# IOa.net
KiCad netlist of a schematic drawn in Altium Designer
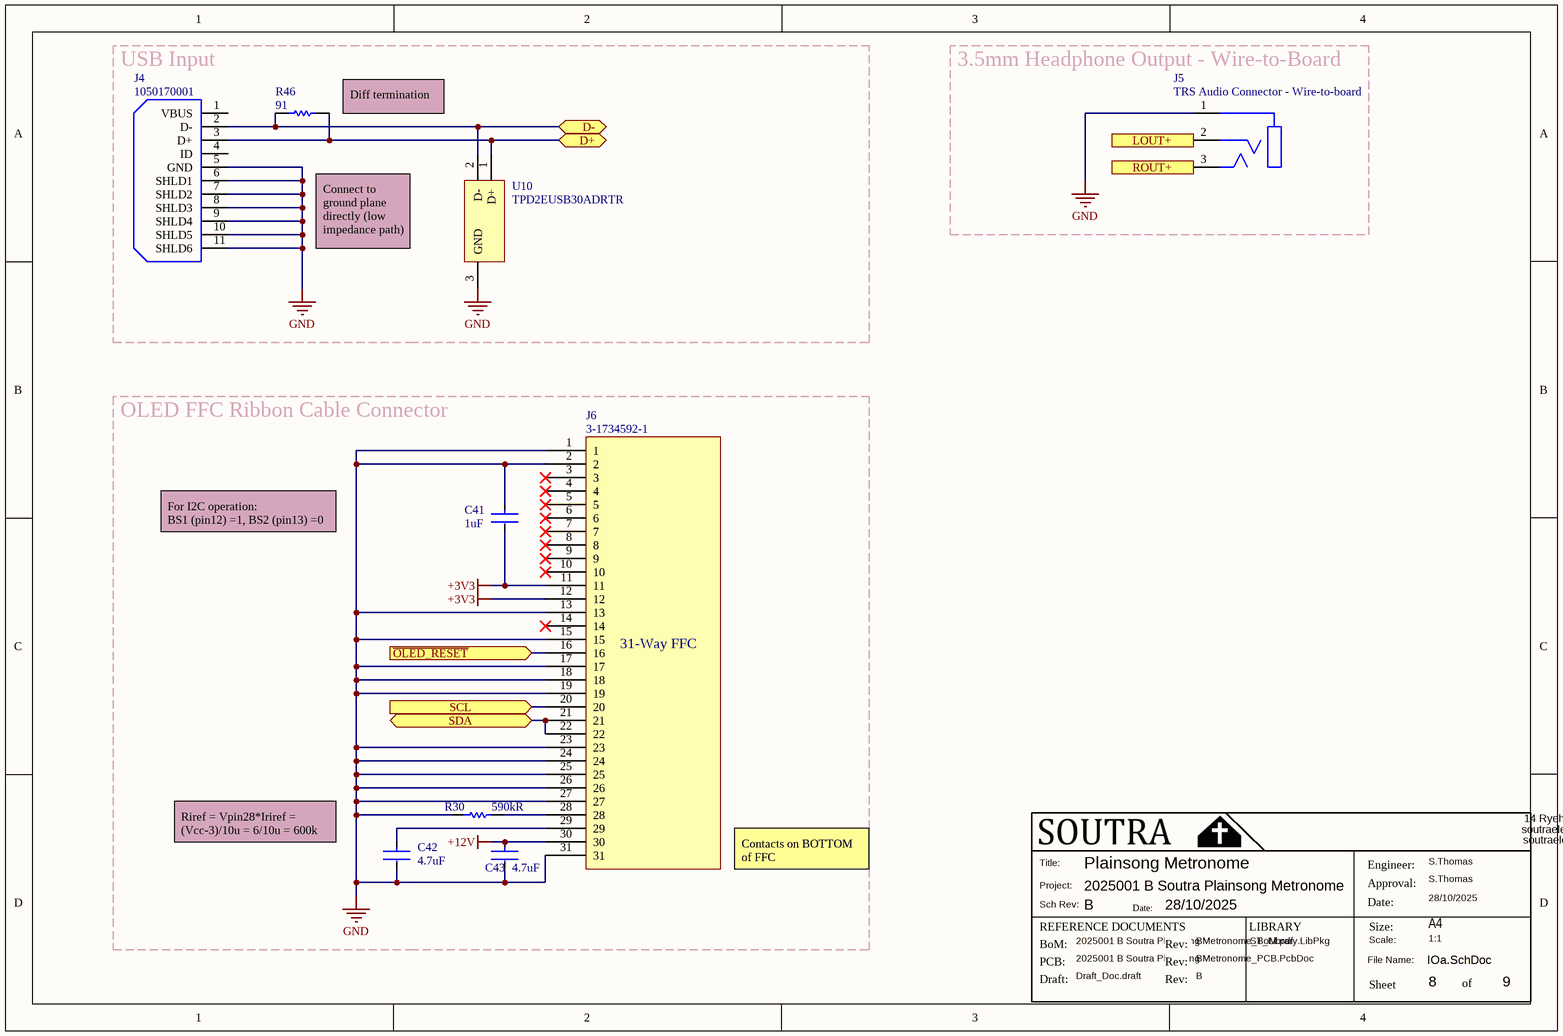
[diagram p0: IOa.SchDoc]

(export (version "E")
  (design (tool "Eeschema 10.0.6"))
  (components
    (comp (ref "C41")
      (value "1uF")
      (footprint "CAPC1005X06L")
      (fields
        (field (name "MANUFACTURER") "Yageo")
        (field (name "MANUFACTURER PART NUMBER") "CC0402KRX5R6BB105")
        (field (name "ALTERNATIVE PART") "0402ZD105KAT2A")
      )
      (libsource (lib "ST_Library") (part "CC0402KRX5R6BB105"))
    )
    (comp (ref "C42")
      (value "4.7uF")
      (footprint "CC1206-IPC_A")
      (fields
        (field (name "MANUFACTURER") "Samsung")
        (field (name "MANUFACTURER PART NUMBER") "CL31B475KAHNNNE")
      )
      (libsource (lib "ST_Library") (part "CL31B475KAHNNNE"))
    )
    (comp (ref "C43")
      (value "4.7uF")
      (footprint "CC1206-IPC_A")
      (fields
        (field (name "MANUFACTURER") "Samsung")
        (field (name "MANUFACTURER PART NUMBER") "CL31B475KAHNNNE")
      )
      (libsource (lib "ST_Library") (part "CL31B475KAHNNNE"))
    )
    (comp (ref "J4")
      (value "1050170001")
      (footprint "1050170001_USB-MICRO-B_V")
      (fields (field (name "MANUFACTURER PART NUMBER") "105017-0001") (field (name "MANUFACTURER") "Molex"))
      (libsource (lib "ST_Library") (part "1050170001"))
    )
    (comp (ref "J5")
      (value "TRS Audio Connector - Wire-to-board")
      (footprint "J_GENERIC_PIN-HEADER_2.54_1X3")
      (libsource (lib "ST_Library") (part "J_AUDIO_TRS"))
    )
    (comp (ref "J6")
      (value "3-1734592-1")
      (footprint "AMP-TE_3-1734592-1")
      (fields (field (name "MANUFACTURER") "TE Connectivity"))
      (libsource (lib "ST_Library") (part "3-1734592-1"))
    )
    (comp (ref "R30")
      (value "590kR")
      (footprint "RESC_0402_1005X40X25LL05T10")
      (fields
        (field (name "MANUFACTURER") "Yageo")
        (field (name "MANUFACTURER PART NUMBER") "RC0402FR-07590KL")
        (field (name "TOLERANCE") "1%")
      )
      (libsource (lib "ST_Library") (part "RC0402FR-07590KL"))
    )
    (comp (ref "R46")
      (value "91")
      (footprint "RESC_0603_1608X06L")
      (description "Res Thick Film 0603 91 Ohm 1% 0.25W(1/4W) ±100ppm/C Pad SMD Automotive T/R")
      (fields
        (field (name "MANUFACTURER") "Panasonic")
        (field (name "MANUFACTURER PART NUMBER") "ERJ-PA3F91R0V")
      )
      (libsource (lib "ST_Library") (part "ERJ-PA3F91R0V"))
    )
    (comp (ref "U10")
      (value "TPD2EUSB30ADRTR")
      (footprint "DRT0003A")
      (fields (field (name "MANUFACTURER") "Texas Instruments"))
      (libsource (lib "ST_Library") (part "TPD2EUSB30ADRTR"))
    )
  )
  (nets
    (net (code "1") (name "+3V3") (class "Default")
      (node (ref "C41") (pin "2") (pinfunction "2_2") (pintype "passive"))
      (node (ref "J6") (pin "11") (pinfunction "11_11") (pintype "passive"))
      (node (ref "J6") (pin "12") (pinfunction "12_12") (pintype "passive"))
    )
    (net (code "2") (name "+12V") (class "Default")
      (node (ref "C43") (pin "1") (pinfunction "1_1") (pintype "passive"))
      (node (ref "J6") (pin "30") (pinfunction "30_30") (pintype "passive"))
    )
    (net (code "3") (name "/D+") (class "Default")
      (node (ref "J4") (pin "3") (pinfunction "D+_3") (pintype "passive"))
      (node (ref "R46") (pin "2") (pinfunction "2_2") (pintype "passive"))
      (node (ref "U10") (pin "1") (pinfunction "D+_1") (pintype "passive"))
    )
    (net (code "4") (name "/D-") (class "Default")
      (node (ref "J4") (pin "2") (pinfunction "D-_2") (pintype "passive"))
      (node (ref "R46") (pin "1") (pinfunction "1_1") (pintype "passive"))
      (node (ref "U10") (pin "2") (pinfunction "D-_2") (pintype "passive"))
    )
    (net (code "5") (name "/LOUT+") (class "Default")
      (node (ref "J5") (pin "2") (pinfunction "2_2") (pintype "passive"))
    )
    (net (code "6") (name "/ROUT+") (class "Default")
      (node (ref "J5") (pin "3") (pinfunction "3_3") (pintype "passive"))
    )
    (net (code "7") (name "/SCL") (class "Default")
      (node (ref "J6") (pin "20") (pinfunction "20_20") (pintype "passive"))
    )
    (net (code "8") (name "/SDA") (class "Default")
      (node (ref "J6") (pin "21") (pinfunction "21_21") (pintype "passive"))
      (node (ref "J6") (pin "22") (pinfunction "22_22") (pintype "passive"))
    )
    (net (code "9") (name "/~{OLED_RESET}") (class "Default")
      (node (ref "J6") (pin "16") (pinfunction "16_16") (pintype "passive"))
    )
    (net (code "10") (name "GND") (class "Default")
      (node (ref "C41") (pin "1") (pinfunction "1_1") (pintype "passive"))
      (node (ref "C42") (pin "2") (pinfunction "2_2") (pintype "passive"))
      (node (ref "C43") (pin "2") (pinfunction "2_2") (pintype "passive"))
      (node (ref "J4") (pin "10") (pinfunction "SHLD5_10") (pintype "passive"))
      (node (ref "J4") (pin "11") (pinfunction "SHLD6_11") (pintype "passive"))
      (node (ref "J4") (pin "5") (pinfunction "GND_5") (pintype "passive"))
      (node (ref "J4") (pin "6") (pinfunction "SHLD1_6") (pintype "passive"))
      (node (ref "J4") (pin "7") (pinfunction "SHLD2_7") (pintype "passive"))
      (node (ref "J4") (pin "8") (pinfunction "SHLD3_8") (pintype "passive"))
      (node (ref "J4") (pin "9") (pinfunction "SHLD4_9") (pintype "passive"))
      (node (ref "J5") (pin "1") (pinfunction "1_1") (pintype "passive"))
      (node (ref "J6") (pin "1") (pinfunction "1_1") (pintype "passive"))
      (node (ref "J6") (pin "13") (pinfunction "13_13") (pintype "passive"))
      (node (ref "J6") (pin "15") (pinfunction "15_15") (pintype "passive"))
      (node (ref "J6") (pin "17") (pinfunction "17_17") (pintype "passive"))
      (node (ref "J6") (pin "18") (pinfunction "18_18") (pintype "passive"))
      (node (ref "J6") (pin "19") (pinfunction "19_19") (pintype "passive"))
      (node (ref "J6") (pin "2") (pinfunction "2_2") (pintype "passive"))
      (node (ref "J6") (pin "23") (pinfunction "23_23") (pintype "passive"))
      (node (ref "J6") (pin "24") (pinfunction "24_24") (pintype "passive"))
      (node (ref "J6") (pin "25") (pinfunction "25_25") (pintype "passive"))
      (node (ref "J6") (pin "26") (pinfunction "26_26") (pintype "passive"))
      (node (ref "J6") (pin "27") (pinfunction "27_27") (pintype "passive"))
      (node (ref "J6") (pin "31") (pinfunction "31_31") (pintype "passive"))
      (node (ref "R30") (pin "1") (pinfunction "1_1") (pintype "passive"))
      (node (ref "U10") (pin "3") (pinfunction "GND_3") (pintype "power_in"))
    )
    (net (code "11") (name "Net-(C42-Pad1)") (class "Default")
      (node (ref "C42") (pin "1") (pinfunction "1_1") (pintype "passive"))
      (node (ref "J6") (pin "29") (pinfunction "29_29") (pintype "passive"))
    )
    (net (code "12") (name "Net-(J6-Pad28)") (class "Default")
      (node (ref "J6") (pin "28") (pinfunction "28_28") (pintype "passive"))
      (node (ref "R30") (pin "2") (pinfunction "2_2") (pintype "passive"))
    )
    (net (code "13") (name "unconnected-(J4-ID-Pad4)") (class "Default")
      (node (ref "J4") (pin "4") (pinfunction "ID_4") (pintype "passive"))
    )
    (net (code "14") (name "unconnected-(J4-VBUS-Pad1)") (class "Default")
      (node (ref "J4") (pin "1") (pinfunction "VBUS_1") (pintype "passive"))
    )
    (net (code "15") (name "unconnected-(J6-Pad3)") (class "Default")
      (node (ref "J6") (pin "3") (pinfunction "3_3") (pintype "passive+no_connect"))
    )
    (net (code "16") (name "unconnected-(J6-Pad4)") (class "Default")
      (node (ref "J6") (pin "4") (pinfunction "4_4") (pintype "passive+no_connect"))
    )
    (net (code "17") (name "unconnected-(J6-Pad5)") (class "Default")
      (node (ref "J6") (pin "5") (pinfunction "5_5") (pintype "passive+no_connect"))
    )
    (net (code "18") (name "unconnected-(J6-Pad6)") (class "Default")
      (node (ref "J6") (pin "6") (pinfunction "6_6") (pintype "passive+no_connect"))
    )
    (net (code "19") (name "unconnected-(J6-Pad7)") (class "Default")
      (node (ref "J6") (pin "7") (pinfunction "7_7") (pintype "passive+no_connect"))
    )
    (net (code "20") (name "unconnected-(J6-Pad8)") (class "Default")
      (node (ref "J6") (pin "8") (pinfunction "8_8") (pintype "passive+no_connect"))
    )
    (net (code "21") (name "unconnected-(J6-Pad9)") (class "Default")
      (node (ref "J6") (pin "9") (pinfunction "9_9") (pintype "passive+no_connect"))
    )
    (net (code "22") (name "unconnected-(J6-Pad10)") (class "Default")
      (node (ref "J6") (pin "10") (pinfunction "10_10") (pintype "passive+no_connect"))
    )
    (net (code "23") (name "unconnected-(J6-Pad14)") (class "Default")
      (node (ref "J6") (pin "14") (pinfunction "14_14") (pintype "passive+no_connect"))
    )
  )
)
